# joyAnalog.net
KiCad netlist of a schematic drawn in EAGLE
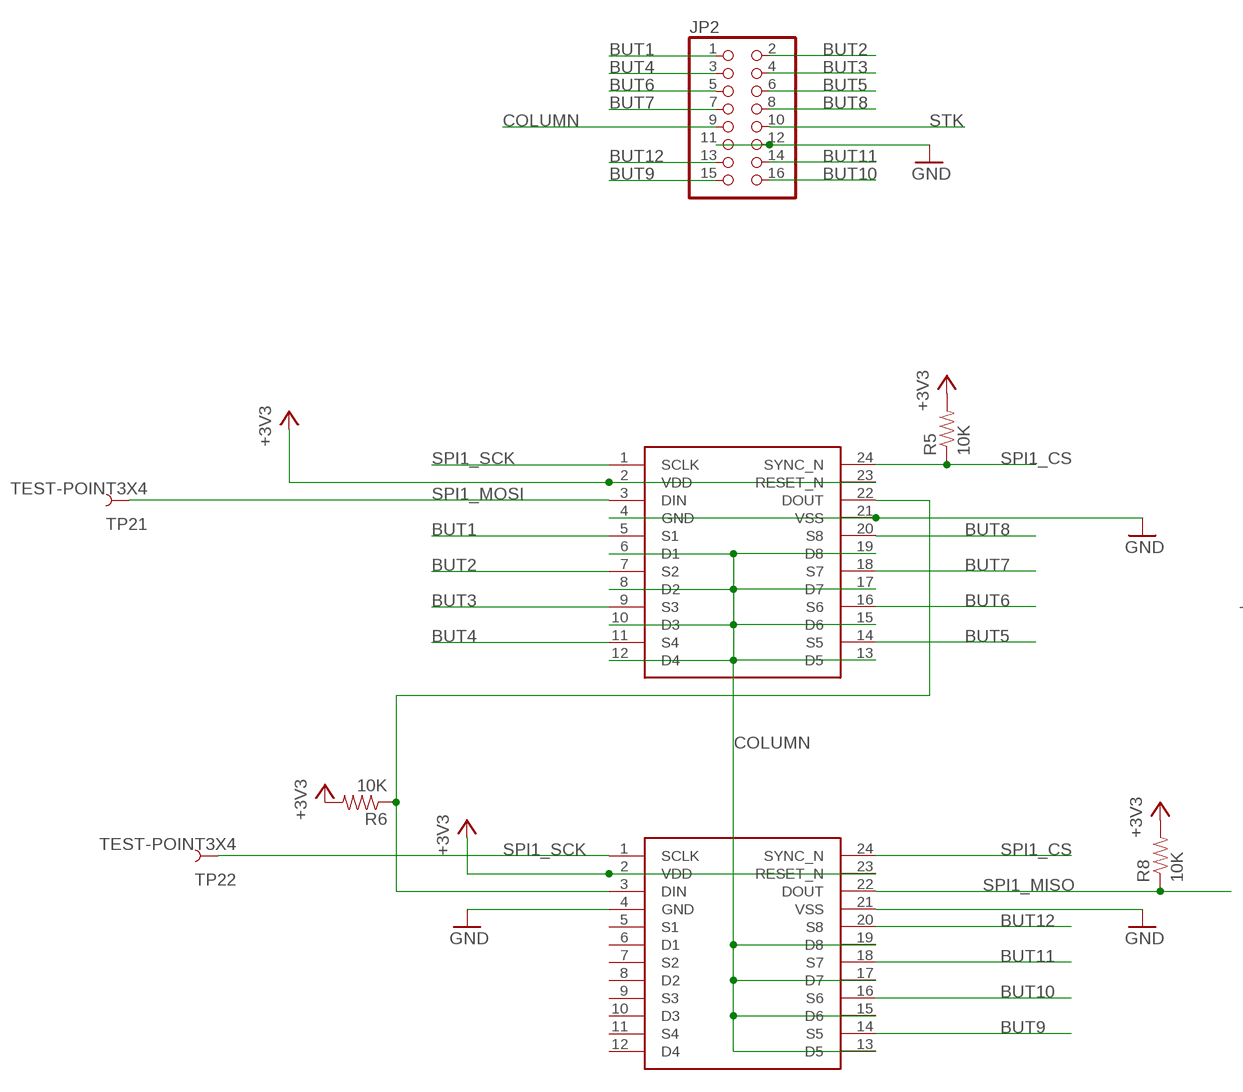
[diagram p0: schematic, sheet 1, part 1 of 2]
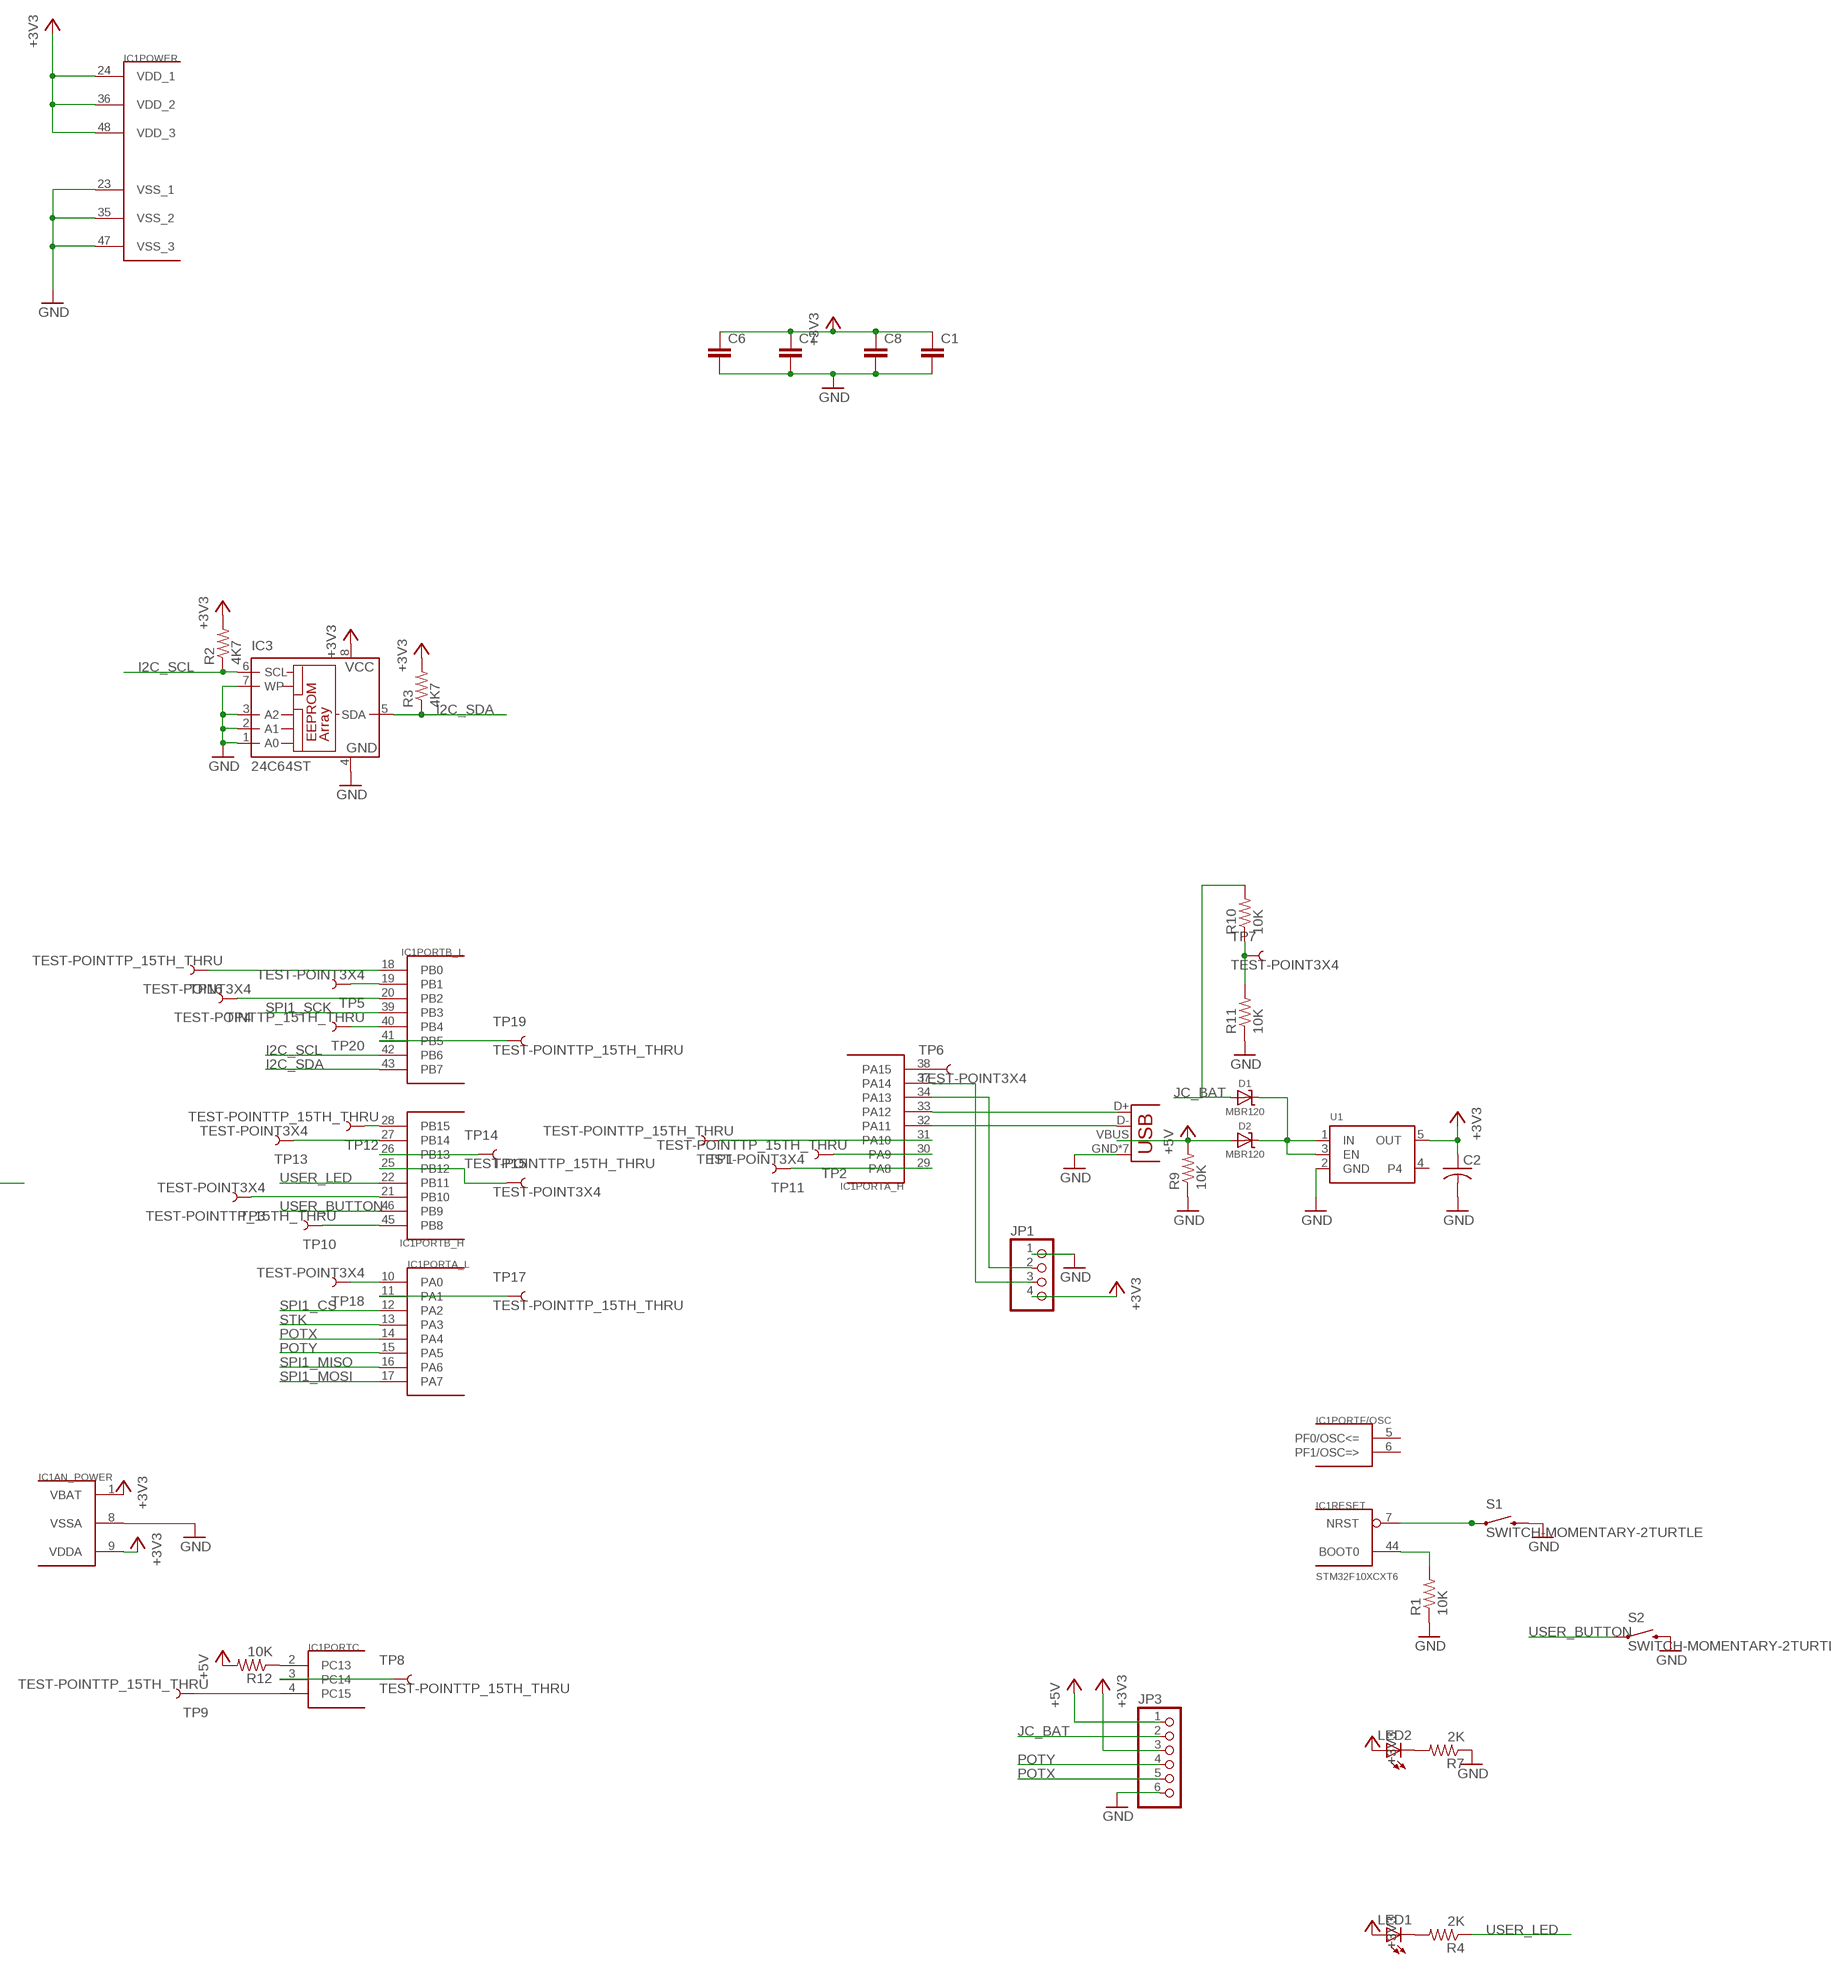
[diagram p1: schematic, sheet 1, part 2 of 2]

(export (version "E")
  (design (tool "Eeschema 10.0.6"))
  (components
    (comp (ref "C1")
      (value "CAP0805")
      (footprint "eagle-import:0805")
      (libsource (lib "eagle-import") (part "CAP0805"))
    )
    (comp (ref "C2")
      (value "C-USC1210")
      (footprint "eagle-import:C1210")
      (libsource (lib "eagle-import") (part "C-USC1210"))
    )
    (comp (ref "C6")
      (value "CAP0805")
      (footprint "eagle-import:0805")
      (libsource (lib "eagle-import") (part "CAP0805"))
    )
    (comp (ref "C7")
      (value "CAP0805")
      (footprint "eagle-import:0805")
      (libsource (lib "eagle-import") (part "CAP0805"))
    )
    (comp (ref "C8")
      (value "CAP0805")
      (footprint "eagle-import:0805")
      (libsource (lib "eagle-import") (part "CAP0805"))
    )
    (comp (ref "D1")
      (value "MBR120")
      (footprint "eagle-import:SOD-123")
      (libsource (lib "eagle-import") (part "DIODE-SCHOTTKYSOD-123"))
    )
    (comp (ref "D2")
      (value "MBR120")
      (footprint "eagle-import:SOD-123")
      (libsource (lib "eagle-import") (part "DIODE-SCHOTTKYSOD-123"))
    )
    (comp (ref "IC1")
      (value "STM32F10XCXT6")
      (footprint "eagle-import:TQFP48")
      (libsource (lib "eagle-import") (part "STM32F10XCXT6"))
    )
    (comp (ref "IC3")
      (value "24C64ST")
      (footprint "eagle-import:TSSOP8")
      (fields (field (name "MPN") "CAT24C64YI-GT3"))
      (libsource (lib "eagle-import") (part "24STC64"))
    )
    (comp (ref "JP1")
      (value "PINHD-1X4")
      (footprint "eagle-import:1X04")
      (libsource (lib "eagle-import") (part "PINHD-1X4"))
    )
    (comp (ref "JP2")
      (value "PINHD-2X8")
      (footprint "eagle-import:2X08")
      (libsource (lib "eagle-import") (part "PINHD-2X8"))
    )
    (comp (ref "JP3")
      (value "PINHD-1X6CB")
      (footprint "eagle-import:1X06-CLEANBIG")
      (libsource (lib "eagle-import") (part "PINHD-1X6CB"))
    )
    (comp (ref "LED1")
      (value "LEDCHIP-LED0805")
      (footprint "eagle-import:CHIP-LED0805")
      (libsource (lib "eagle-import") (part "LEDCHIP-LED0805"))
    )
    (comp (ref "LED2")
      (value "LEDCHIP-LED0805")
      (footprint "eagle-import:CHIP-LED0805")
      (libsource (lib "eagle-import") (part "LEDCHIP-LED0805"))
    )
    (comp (ref "R1")
      (value "10K")
      (footprint "eagle-import:0805")
      (libsource (lib "eagle-import") (part "RESISTOR0805-RES"))
    )
    (comp (ref "R2")
      (value "4K7")
      (footprint "eagle-import:0805")
      (libsource (lib "eagle-import") (part "RESISTOR0805-RES"))
    )
    (comp (ref "R3")
      (value "4K7")
      (footprint "eagle-import:0805")
      (libsource (lib "eagle-import") (part "RESISTOR0805-RES"))
    )
    (comp (ref "R4")
      (value "2K")
      (footprint "eagle-import:0805")
      (libsource (lib "eagle-import") (part "RESISTOR0805-RES"))
    )
    (comp (ref "R5")
      (value "10K")
      (footprint "eagle-import:0805")
      (libsource (lib "eagle-import") (part "RESISTOR0805-RES"))
    )
    (comp (ref "R6")
      (value "10K")
      (footprint "eagle-import:0805")
      (libsource (lib "eagle-import") (part "RESISTOR0805-RES"))
    )
    (comp (ref "R7")
      (value "2K")
      (footprint "eagle-import:0805")
      (libsource (lib "eagle-import") (part "RESISTOR0805-RES"))
    )
    (comp (ref "R8")
      (value "10K")
      (footprint "eagle-import:0805")
      (libsource (lib "eagle-import") (part "RESISTOR0805-RES"))
    )
    (comp (ref "R9")
      (value "10K")
      (footprint "eagle-import:0805")
      (libsource (lib "eagle-import") (part "RESISTOR0805-RES"))
    )
    (comp (ref "R10")
      (value "10K")
      (footprint "eagle-import:0805")
      (libsource (lib "eagle-import") (part "RESISTOR0805-RES"))
    )
    (comp (ref "R11")
      (value "10K")
      (footprint "eagle-import:0805")
      (libsource (lib "eagle-import") (part "RESISTOR0805-RES"))
    )
    (comp (ref "R12")
      (value "10K")
      (footprint "eagle-import:0805")
      (libsource (lib "eagle-import") (part "RESISTOR0805-RES"))
    )
    (comp (ref "S1")
      (value "SWITCH-MOMENTARY-2TURTLE")
      (footprint "eagle-import:KMR2")
      (libsource (lib "eagle-import") (part "SWITCH-MOMENTARY-2TURTLE"))
    )
    (comp (ref "S2")
      (value "SWITCH-MOMENTARY-2TURTLE")
      (footprint "eagle-import:KMR2")
      (libsource (lib "eagle-import") (part "SWITCH-MOMENTARY-2TURTLE"))
    )
    (comp (ref "TP1")
      (value "TEST-POINTTP_15TH_THRU")
      (footprint "eagle-import:TP_15TH")
      (libsource (lib "eagle-import") (part "pth testpoint_TEST-POINTTP_15TH_THRU"))
    )
    (comp (ref "TP2")
      (value "TEST-POINTTP_15TH_THRU")
      (footprint "eagle-import:TP_15TH")
      (libsource (lib "eagle-import") (part "pth testpoint_TEST-POINTTP_15TH_THRU"))
    )
    (comp (ref "TP3")
      (value "TEST-POINT3X4")
      (footprint "eagle-import:PAD.03X.04")
      (libsource (lib "eagle-import") (part "TEST-POINT3X4"))
    )
    (comp (ref "TP4")
      (value "TEST-POINT3X4")
      (footprint "eagle-import:PAD.03X.04")
      (libsource (lib "eagle-import") (part "TEST-POINT3X4"))
    )
    (comp (ref "TP5")
      (value "TEST-POINT3X4")
      (footprint "eagle-import:PAD.03X.04")
      (libsource (lib "eagle-import") (part "TEST-POINT3X4"))
    )
    (comp (ref "TP6")
      (value "TEST-POINT3X4")
      (footprint "eagle-import:PAD.03X.04")
      (libsource (lib "eagle-import") (part "TEST-POINT3X4"))
    )
    (comp (ref "TP7")
      (value "TEST-POINT3X4")
      (footprint "eagle-import:PAD.03X.04")
      (libsource (lib "eagle-import") (part "TEST-POINT3X4"))
    )
    (comp (ref "TP8")
      (value "TEST-POINTTP_15TH_THRU")
      (footprint "eagle-import:TP_15TH")
      (libsource (lib "eagle-import") (part "pth testpoint_TEST-POINTTP_15TH_THRU"))
    )
    (comp (ref "TP9")
      (value "TEST-POINTTP_15TH_THRU")
      (footprint "eagle-import:TP_15TH")
      (libsource (lib "eagle-import") (part "pth testpoint_TEST-POINTTP_15TH_THRU"))
    )
    (comp (ref "TP10")
      (value "TEST-POINTTP_15TH_THRU")
      (footprint "eagle-import:TP_15TH")
      (libsource (lib "eagle-import") (part "pth testpoint_TEST-POINTTP_15TH_THRU"))
    )
    (comp (ref "TP11")
      (value "TEST-POINT3X4")
      (footprint "eagle-import:PAD.03X.04")
      (libsource (lib "eagle-import") (part "TEST-POINT3X4"))
    )
    (comp (ref "TP12")
      (value "TEST-POINTTP_15TH_THRU")
      (footprint "eagle-import:TP_15TH")
      (libsource (lib "eagle-import") (part "pth testpoint_TEST-POINTTP_15TH_THRU"))
    )
    (comp (ref "TP13")
      (value "TEST-POINT3X4")
      (footprint "eagle-import:PAD.03X.04")
      (libsource (lib "eagle-import") (part "TEST-POINT3X4"))
    )
    (comp (ref "TP14")
      (value "TEST-POINTTP_15TH_THRU")
      (footprint "eagle-import:TP_15TH")
      (libsource (lib "eagle-import") (part "pth testpoint_TEST-POINTTP_15TH_THRU"))
    )
    (comp (ref "TP15")
      (value "TEST-POINT3X4")
      (footprint "eagle-import:PAD.03X.04")
      (libsource (lib "eagle-import") (part "TEST-POINT3X4"))
    )
    (comp (ref "TP16")
      (value "TEST-POINTTP_15TH_THRU")
      (footprint "eagle-import:TP_15TH")
      (libsource (lib "eagle-import") (part "pth testpoint_TEST-POINTTP_15TH_THRU"))
    )
    (comp (ref "TP17")
      (value "TEST-POINTTP_15TH_THRU")
      (footprint "eagle-import:TP_15TH")
      (libsource (lib "eagle-import") (part "pth testpoint_TEST-POINTTP_15TH_THRU"))
    )
    (comp (ref "TP18")
      (value "TEST-POINT3X4")
      (footprint "eagle-import:PAD.03X.04")
      (libsource (lib "eagle-import") (part "TEST-POINT3X4"))
    )
    (comp (ref "TP19")
      (value "TEST-POINTTP_15TH_THRU")
      (footprint "eagle-import:TP_15TH")
      (libsource (lib "eagle-import") (part "pth testpoint_TEST-POINTTP_15TH_THRU"))
    )
    (comp (ref "TP20")
      (value "TEST-POINTTP_15TH_THRU")
      (footprint "eagle-import:TP_15TH")
      (libsource (lib "eagle-import") (part "pth testpoint_TEST-POINTTP_15TH_THRU"))
    )
    (comp (ref "TP21")
      (value "TEST-POINT3X4")
      (footprint "eagle-import:PAD.03X.04")
      (libsource (lib "eagle-import") (part "TEST-POINT3X4"))
    )
    (comp (ref "TP22")
      (value "TEST-POINT3X4")
      (footprint "eagle-import:PAD.03X.04")
      (libsource (lib "eagle-import") (part "TEST-POINT3X4"))
    )
    (comp (ref "U$3")
      (value "ADG714_DEV")
      (footprint "eagle-import:TSSOP-24")
      (libsource (lib "eagle-import") (part "ADG714_DEV"))
    )
    (comp (ref "U$4")
      (value "ADG714_DEV")
      (footprint "eagle-import:TSSOP-24")
      (libsource (lib "eagle-import") (part "ADG714_DEV"))
    )
    (comp (ref "U1")
      (value "VREG_SOT23-5")
      (footprint "eagle-import:SOT23-5")
      (libsource (lib "eagle-import") (part "VREG_SOT23-5"))
    )
    (comp (ref "X1")
      (value "USB-MICROB")
      (footprint "eagle-import:USB-MICROB")
      (libsource (lib "eagle-import") (part "USB-MICROB"))
    )
  )
  (nets
    (net (code "1") (name "+3V3") (class "Default")
      (node (ref "C1") (pin "1") (pinfunction "1_1") (pintype "passive"))
      (node (ref "C2") (pin "1") (pinfunction "1_1") (pintype "passive"))
      (node (ref "C6") (pin "1") (pinfunction "1_1") (pintype "passive"))
      (node (ref "C7") (pin "1") (pinfunction "1_1") (pintype "passive"))
      (node (ref "C8") (pin "1") (pinfunction "1_1") (pintype "passive"))
      (node (ref "IC1") (pin "1") (pinfunction "VBAT_1") (pintype "power_in"))
      (node (ref "IC1") (pin "24") (pinfunction "VDD_1_24") (pintype "power_in"))
      (node (ref "IC1") (pin "36") (pinfunction "VDD_2_36") (pintype "power_in"))
      (node (ref "IC1") (pin "48") (pinfunction "VDD_3_48") (pintype "power_in"))
      (node (ref "IC1") (pin "9") (pinfunction "VDDA_9") (pintype "power_in"))
      (node (ref "IC3") (pin "8") (pinfunction "VCC_8") (pintype "power_in"))
      (node (ref "JP1") (pin "4") (pinfunction "4_4") (pintype "passive"))
      (node (ref "JP3") (pin "3") (pinfunction "3_3") (pintype "passive"))
      (node (ref "LED1") (pin "A") (pinfunction "A_A") (pintype "passive"))
      (node (ref "LED2") (pin "A") (pinfunction "A_A") (pintype "passive"))
      (node (ref "R2") (pin "2") (pinfunction "2_2") (pintype "passive"))
      (node (ref "R3") (pin "2") (pinfunction "2_2") (pintype "passive"))
      (node (ref "R5") (pin "2") (pinfunction "2_2") (pintype "passive"))
      (node (ref "R6") (pin "2") (pinfunction "2_2") (pintype "passive"))
      (node (ref "R8") (pin "2") (pinfunction "2_2") (pintype "passive"))
      (node (ref "U$3") (pin "2") (pinfunction "VDD_2") (pintype "bidirectional"))
      (node (ref "U$3") (pin "23") (pinfunction "RESET_N_23") (pintype "bidirectional"))
      (node (ref "U$4") (pin "2") (pinfunction "VDD_2") (pintype "bidirectional"))
      (node (ref "U$4") (pin "23") (pinfunction "RESET_N_23") (pintype "bidirectional"))
      (node (ref "U1") (pin "5") (pinfunction "OUT_5") (pintype "power_in"))
    )
    (net (code "2") (name "+5V") (class "Default")
      (node (ref "D2") (pin "A") (pinfunction "A_A") (pintype "passive"))
      (node (ref "JP3") (pin "1") (pinfunction "1_1") (pintype "passive"))
      (node (ref "R12") (pin "2") (pinfunction "2_2") (pintype "passive"))
      (node (ref "R9") (pin "2") (pinfunction "2_2") (pintype "passive"))
      (node (ref "X1") (pin "VBUS") (pinfunction "VBUS_VBUS") (pintype "bidirectional"))
    )
    (net (code "3") (name "/BUT1") (class "Default")
      (node (ref "JP2") (pin "1") (pinfunction "1_1") (pintype "passive"))
      (node (ref "U$3") (pin "5") (pinfunction "S1_5") (pintype "bidirectional"))
    )
    (net (code "4") (name "/BUT2") (class "Default")
      (node (ref "JP2") (pin "2") (pinfunction "2_2") (pintype "passive"))
      (node (ref "U$3") (pin "7") (pinfunction "S2_7") (pintype "bidirectional"))
    )
    (net (code "5") (name "/BUT3") (class "Default")
      (node (ref "JP2") (pin "4") (pinfunction "4_4") (pintype "passive"))
      (node (ref "U$3") (pin "9") (pinfunction "S3_9") (pintype "bidirectional"))
    )
    (net (code "6") (name "/BUT4") (class "Default")
      (node (ref "JP2") (pin "3") (pinfunction "3_3") (pintype "passive"))
      (node (ref "U$3") (pin "11") (pinfunction "S4_11") (pintype "bidirectional"))
    )
    (net (code "7") (name "/BUT5") (class "Default")
      (node (ref "JP2") (pin "6") (pinfunction "6_6") (pintype "passive"))
      (node (ref "U$3") (pin "14") (pinfunction "S5_14") (pintype "bidirectional"))
    )
    (net (code "8") (name "/BUT6") (class "Default")
      (node (ref "JP2") (pin "5") (pinfunction "5_5") (pintype "passive"))
      (node (ref "U$3") (pin "16") (pinfunction "S6_16") (pintype "bidirectional"))
    )
    (net (code "9") (name "/BUT7") (class "Default")
      (node (ref "JP2") (pin "7") (pinfunction "7_7") (pintype "passive"))
      (node (ref "U$3") (pin "18") (pinfunction "S7_18") (pintype "bidirectional"))
    )
    (net (code "10") (name "/BUT8") (class "Default")
      (node (ref "JP2") (pin "8") (pinfunction "8_8") (pintype "passive"))
      (node (ref "U$3") (pin "20") (pinfunction "S8_20") (pintype "bidirectional"))
    )
    (net (code "11") (name "/BUT9") (class "Default")
      (node (ref "JP2") (pin "15") (pinfunction "15_15") (pintype "passive"))
      (node (ref "U$4") (pin "14") (pinfunction "S5_14") (pintype "bidirectional"))
    )
    (net (code "12") (name "/BUT10") (class "Default")
      (node (ref "JP2") (pin "16") (pinfunction "16_16") (pintype "passive"))
      (node (ref "U$4") (pin "16") (pinfunction "S6_16") (pintype "bidirectional"))
    )
    (net (code "13") (name "/BUT11") (class "Default")
      (node (ref "JP2") (pin "14") (pinfunction "14_14") (pintype "passive"))
      (node (ref "U$4") (pin "18") (pinfunction "S7_18") (pintype "bidirectional"))
    )
    (net (code "14") (name "/BUT12") (class "Default")
      (node (ref "JP2") (pin "13") (pinfunction "13_13") (pintype "passive"))
      (node (ref "U$4") (pin "20") (pinfunction "S8_20") (pintype "bidirectional"))
    )
    (net (code "15") (name "/COLUMN") (class "Default")
      (node (ref "JP2") (pin "9") (pinfunction "9_9") (pintype "passive"))
      (node (ref "U$3") (pin "10") (pinfunction "D3_10") (pintype "bidirectional"))
      (node (ref "U$3") (pin "12") (pinfunction "D4_12") (pintype "bidirectional"))
      (node (ref "U$3") (pin "13") (pinfunction "D5_13") (pintype "bidirectional"))
      (node (ref "U$3") (pin "15") (pinfunction "D6_15") (pintype "bidirectional"))
      (node (ref "U$3") (pin "17") (pinfunction "D7_17") (pintype "bidirectional"))
      (node (ref "U$3") (pin "19") (pinfunction "D8_19") (pintype "bidirectional"))
      (node (ref "U$3") (pin "6") (pinfunction "D1_6") (pintype "bidirectional"))
      (node (ref "U$3") (pin "8") (pinfunction "D2_8") (pintype "bidirectional"))
      (node (ref "U$4") (pin "13") (pinfunction "D5_13") (pintype "bidirectional"))
      (node (ref "U$4") (pin "15") (pinfunction "D6_15") (pintype "bidirectional"))
      (node (ref "U$4") (pin "17") (pinfunction "D7_17") (pintype "bidirectional"))
      (node (ref "U$4") (pin "19") (pinfunction "D8_19") (pintype "bidirectional"))
    )
    (net (code "16") (name "/I2C_SCL") (class "Default")
      (node (ref "IC1") (pin "42") (pinfunction "PB6_42") (pintype "bidirectional"))
      (node (ref "IC3") (pin "6") (pinfunction "SCL_6") (pintype "input"))
      (node (ref "R2") (pin "1") (pinfunction "1_1") (pintype "passive"))
    )
    (net (code "17") (name "/I2C_SDA") (class "Default")
      (node (ref "IC1") (pin "43") (pinfunction "PB7_43") (pintype "bidirectional"))
      (node (ref "IC3") (pin "5") (pinfunction "SDA_5") (pintype "bidirectional"))
      (node (ref "R3") (pin "1") (pinfunction "1_1") (pintype "passive"))
    )
    (net (code "18") (name "/JC_BAT") (class "Default")
      (node (ref "D1") (pin "A") (pinfunction "A_A") (pintype "passive"))
      (node (ref "JP3") (pin "2") (pinfunction "2_2") (pintype "passive"))
      (node (ref "R10") (pin "2") (pinfunction "2_2") (pintype "passive"))
    )
    (net (code "19") (name "/POTX") (class "Default")
      (node (ref "IC1") (pin "14") (pinfunction "PA4_14") (pintype "bidirectional"))
      (node (ref "JP3") (pin "5") (pinfunction "5_5") (pintype "passive"))
    )
    (net (code "20") (name "/POTY") (class "Default")
      (node (ref "IC1") (pin "15") (pinfunction "PA5_15") (pintype "bidirectional"))
      (node (ref "JP3") (pin "4") (pinfunction "4_4") (pintype "passive"))
    )
    (net (code "21") (name "/SPI1_CS") (class "Default")
      (node (ref "IC1") (pin "12") (pinfunction "PA2_12") (pintype "bidirectional"))
      (node (ref "R5") (pin "1") (pinfunction "1_1") (pintype "passive"))
      (node (ref "U$3") (pin "24") (pinfunction "SYNC_N_24") (pintype "bidirectional"))
      (node (ref "U$4") (pin "24") (pinfunction "SYNC_N_24") (pintype "bidirectional"))
    )
    (net (code "22") (name "/SPI1_MISO") (class "Default")
      (node (ref "IC1") (pin "16") (pinfunction "PA6_16") (pintype "bidirectional"))
      (node (ref "R8") (pin "1") (pinfunction "1_1") (pintype "passive"))
      (node (ref "U$4") (pin "22") (pinfunction "DOUT_22") (pintype "bidirectional"))
    )
    (net (code "23") (name "/SPI1_MOSI") (class "Default")
      (node (ref "IC1") (pin "17") (pinfunction "PA7_17") (pintype "bidirectional"))
      (node (ref "TP21") (pin "P$1") (pinfunction "1_P$1") (pintype "bidirectional"))
      (node (ref "U$3") (pin "3") (pinfunction "DIN_3") (pintype "bidirectional"))
    )
    (net (code "24") (name "/SPI1_SCK") (class "Default")
      (node (ref "IC1") (pin "39") (pinfunction "PB3_39") (pintype "bidirectional"))
      (node (ref "TP22") (pin "P$1") (pinfunction "1_P$1") (pintype "bidirectional"))
      (node (ref "U$3") (pin "1") (pinfunction "SCLK_1") (pintype "bidirectional"))
      (node (ref "U$4") (pin "1") (pinfunction "SCLK_1") (pintype "bidirectional"))
    )
    (net (code "25") (name "/STK") (class "Default")
      (node (ref "IC1") (pin "13") (pinfunction "PA3_13") (pintype "bidirectional"))
      (node (ref "JP2") (pin "10") (pinfunction "10_10") (pintype "passive"))
    )
    (net (code "26") (name "/USER_BUTTON") (class "Default")
      (node (ref "IC1") (pin "46") (pinfunction "PB9_46") (pintype "bidirectional"))
      (node (ref "S2") (pin "1") (pinfunction "1_1") (pintype "passive"))
    )
    (net (code "27") (name "/USER_LED") (class "Default")
      (node (ref "IC1") (pin "22") (pinfunction "PB11_22") (pintype "bidirectional"))
      (node (ref "R4") (pin "1") (pinfunction "1_1") (pintype "passive"))
    )
    (net (code "28") (name "GND") (class "Default")
      (node (ref "C1") (pin "2") (pinfunction "2_2") (pintype "passive"))
      (node (ref "C2") (pin "2") (pinfunction "2_2") (pintype "passive"))
      (node (ref "C6") (pin "2") (pinfunction "2_2") (pintype "passive"))
      (node (ref "C7") (pin "2") (pinfunction "2_2") (pintype "passive"))
      (node (ref "C8") (pin "2") (pinfunction "2_2") (pintype "passive"))
      (node (ref "IC1") (pin "23") (pinfunction "VSS_1_23") (pintype "power_in"))
      (node (ref "IC1") (pin "35") (pinfunction "VSS_2_35") (pintype "power_in"))
      (node (ref "IC1") (pin "47") (pinfunction "VSS_3_47") (pintype "power_in"))
      (node (ref "IC1") (pin "8") (pinfunction "VSSA_8") (pintype "power_in"))
      (node (ref "IC3") (pin "1") (pinfunction "A0_1") (pintype "input"))
      (node (ref "IC3") (pin "2") (pinfunction "A1_2") (pintype "input"))
      (node (ref "IC3") (pin "3") (pinfunction "A2_3") (pintype "input"))
      (node (ref "IC3") (pin "4") (pinfunction "GND_4") (pintype "power_in"))
      (node (ref "IC3") (pin "7") (pinfunction "WP_7") (pintype "input"))
      (node (ref "JP1") (pin "1") (pinfunction "1_1") (pintype "passive"))
      (node (ref "JP2") (pin "11") (pinfunction "11_11") (pintype "passive"))
      (node (ref "JP2") (pin "12") (pinfunction "12_12") (pintype "passive"))
      (node (ref "JP3") (pin "6") (pinfunction "6_6") (pintype "passive"))
      (node (ref "R1") (pin "1") (pinfunction "1_1") (pintype "passive"))
      (node (ref "R11") (pin "1") (pinfunction "1_1") (pintype "passive"))
      (node (ref "R7") (pin "1") (pinfunction "1_1") (pintype "passive"))
      (node (ref "R9") (pin "1") (pinfunction "1_1") (pintype "passive"))
      (node (ref "S1") (pin "3") (pinfunction "2_3") (pintype "passive"))
      (node (ref "S2") (pin "3") (pinfunction "2_3") (pintype "passive"))
      (node (ref "U$3") (pin "21") (pinfunction "VSS_21") (pintype "bidirectional"))
      (node (ref "U$3") (pin "4") (pinfunction "GND_4") (pintype "bidirectional"))
      (node (ref "U$4") (pin "21") (pinfunction "VSS_21") (pintype "bidirectional"))
      (node (ref "U$4") (pin "4") (pinfunction "GND_4") (pintype "bidirectional"))
      (node (ref "U1") (pin "2") (pinfunction "GND_2") (pintype "power_in"))
      (node (ref "X1") (pin "GND") (pinfunction "GND_GND") (pintype "bidirectional"))
      (node (ref "X1") (pin "P1") (pinfunction "GND_P1") (pintype "bidirectional"))
      (node (ref "X1") (pin "P2") (pinfunction "GND_P2") (pintype "bidirectional"))
      (node (ref "X1") (pin "P3") (pinfunction "GND_P3") (pintype "bidirectional"))
      (node (ref "X1") (pin "P4") (pinfunction "GND_P4") (pintype "bidirectional"))
      (node (ref "X1") (pin "P5") (pinfunction "GND_P5") (pintype "bidirectional"))
      (node (ref "X1") (pin "P6") (pinfunction "GND_P6") (pintype "bidirectional"))
    )
    (net (code "29") (name "Net-(IC1B-PA8)") (class "Default")
      (node (ref "IC1") (pin "29") (pinfunction "PA8_29") (pintype "bidirectional"))
      (node (ref "TP11") (pin "P$1") (pinfunction "1_P$1") (pintype "bidirectional"))
    )
    (net (code "30") (name "Net-(IC1B-PA9)") (class "Default")
      (node (ref "IC1") (pin "30") (pinfunction "PA9_30") (pintype "bidirectional"))
      (node (ref "TP2") (pin "P$1") (pinfunction "1_P$1") (pintype "bidirectional"))
    )
    (net (code "31") (name "Net-(IC1B-PA10)") (class "Default")
      (node (ref "IC1") (pin "31") (pinfunction "PA10_31") (pintype "bidirectional"))
      (node (ref "TP1") (pin "P$1") (pinfunction "1_P$1") (pintype "bidirectional"))
    )
    (net (code "32") (name "Net-(IC1B-PA11)") (class "Default")
      (node (ref "IC1") (pin "32") (pinfunction "PA11_32") (pintype "bidirectional"))
      (node (ref "X1") (pin "D-") (pinfunction "D-_D-") (pintype "bidirectional"))
    )
    (net (code "33") (name "Net-(IC1B-PA12)") (class "Default")
      (node (ref "IC1") (pin "33") (pinfunction "PA12_33") (pintype "bidirectional"))
      (node (ref "X1") (pin "D+") (pinfunction "D+_D+") (pintype "bidirectional"))
    )
    (net (code "34") (name "Net-(IC1B-PA13)") (class "Default")
      (node (ref "IC1") (pin "34") (pinfunction "PA13_34") (pintype "bidirectional"))
      (node (ref "JP1") (pin "2") (pinfunction "2_2") (pintype "passive"))
    )
    (net (code "35") (name "Net-(IC1B-PA14)") (class "Default")
      (node (ref "IC1") (pin "37") (pinfunction "PA14_37") (pintype "bidirectional"))
      (node (ref "JP1") (pin "3") (pinfunction "3_3") (pintype "passive"))
    )
    (net (code "36") (name "Net-(IC1B-PA15)") (class "Default")
      (node (ref "IC1") (pin "38") (pinfunction "PA15_38") (pintype "bidirectional"))
      (node (ref "TP6") (pin "P$1") (pinfunction "1_P$1") (pintype "bidirectional"))
    )
    (net (code "37") (name "Net-(IC1C-PA0)") (class "Default")
      (node (ref "IC1") (pin "10") (pinfunction "PA0_10") (pintype "bidirectional"))
      (node (ref "TP18") (pin "P$1") (pinfunction "1_P$1") (pintype "bidirectional"))
    )
    (net (code "38") (name "Net-(IC1C-PA1)") (class "Default")
      (node (ref "IC1") (pin "11") (pinfunction "PA1_11") (pintype "bidirectional"))
      (node (ref "TP17") (pin "P$1") (pinfunction "1_P$1") (pintype "bidirectional"))
    )
    (net (code "39") (name "Net-(IC1D-PB8)") (class "Default")
      (node (ref "IC1") (pin "45") (pinfunction "PB8_45") (pintype "bidirectional"))
      (node (ref "TP10") (pin "P$1") (pinfunction "1_P$1") (pintype "bidirectional"))
    )
    (net (code "40") (name "Net-(IC1D-PB10)") (class "Default")
      (node (ref "IC1") (pin "21") (pinfunction "PB10_21") (pintype "bidirectional"))
      (node (ref "TP3") (pin "P$1") (pinfunction "1_P$1") (pintype "bidirectional"))
    )
    (net (code "41") (name "Net-(IC1D-PB12)") (class "Default")
      (node (ref "IC1") (pin "25") (pinfunction "PB12_25") (pintype "bidirectional"))
      (node (ref "TP15") (pin "P$1") (pinfunction "1_P$1") (pintype "bidirectional"))
    )
    (net (code "42") (name "Net-(IC1D-PB13)") (class "Default")
      (node (ref "IC1") (pin "26") (pinfunction "PB13_26") (pintype "bidirectional"))
      (node (ref "TP14") (pin "P$1") (pinfunction "1_P$1") (pintype "bidirectional"))
    )
    (net (code "43") (name "Net-(IC1D-PB14)") (class "Default")
      (node (ref "IC1") (pin "27") (pinfunction "PB14_27") (pintype "bidirectional"))
      (node (ref "TP13") (pin "P$1") (pinfunction "1_P$1") (pintype "bidirectional"))
    )
    (net (code "44") (name "Net-(IC1D-PB15)") (class "Default")
      (node (ref "IC1") (pin "28") (pinfunction "PB15_28") (pintype "bidirectional"))
      (node (ref "TP12") (pin "P$1") (pinfunction "1_P$1") (pintype "bidirectional"))
    )
    (net (code "45") (name "Net-(IC1E-PB0)") (class "Default")
      (node (ref "IC1") (pin "18") (pinfunction "PB0_18") (pintype "bidirectional"))
      (node (ref "TP16") (pin "P$1") (pinfunction "1_P$1") (pintype "bidirectional"))
    )
    (net (code "46") (name "Net-(IC1E-PB1)") (class "Default")
      (node (ref "IC1") (pin "19") (pinfunction "PB1_19") (pintype "bidirectional"))
      (node (ref "TP5") (pin "P$1") (pinfunction "1_P$1") (pintype "bidirectional"))
    )
    (net (code "47") (name "Net-(IC1E-PB2)") (class "Default")
      (node (ref "IC1") (pin "20") (pinfunction "PB2_20") (pintype "bidirectional"))
      (node (ref "TP4") (pin "P$1") (pinfunction "1_P$1") (pintype "bidirectional"))
    )
    (net (code "48") (name "Net-(IC1E-PB4)") (class "Default")
      (node (ref "IC1") (pin "40") (pinfunction "PB4_40") (pintype "bidirectional"))
      (node (ref "TP20") (pin "P$1") (pinfunction "1_P$1") (pintype "bidirectional"))
    )
    (net (code "49") (name "Net-(IC1E-PB5)") (class "Default")
      (node (ref "IC1") (pin "41") (pinfunction "PB5_41") (pintype "bidirectional"))
      (node (ref "TP19") (pin "P$1") (pinfunction "1_P$1") (pintype "bidirectional"))
    )
    (net (code "50") (name "Net-(IC1F-PC13)") (class "Default")
      (node (ref "IC1") (pin "2") (pinfunction "PC13_2") (pintype "bidirectional"))
      (node (ref "R12") (pin "1") (pinfunction "1_1") (pintype "passive"))
    )
    (net (code "51") (name "Net-(IC1F-PC14)") (class "Default")
      (node (ref "IC1") (pin "3") (pinfunction "PC14_3") (pintype "bidirectional"))
      (node (ref "TP8") (pin "P$1") (pinfunction "1_P$1") (pintype "bidirectional"))
    )
    (net (code "52") (name "Net-(IC1F-PC15)") (class "Default")
      (node (ref "IC1") (pin "4") (pinfunction "PC15_4") (pintype "bidirectional"))
      (node (ref "TP9") (pin "P$1") (pinfunction "1_P$1") (pintype "bidirectional"))
    )
    (net (code "53") (name "Net-(IC1I-BOOT0)") (class "Default")
      (node (ref "IC1") (pin "44") (pinfunction "BOOT0_44") (pintype "input"))
      (node (ref "R1") (pin "2") (pinfunction "2_2") (pintype "passive"))
    )
    (net (code "54") (name "Net-(IC1I-NRST)") (class "Default")
      (node (ref "IC1") (pin "7") (pinfunction "NRST_7") (pintype "input"))
      (node (ref "S1") (pin "1") (pinfunction "1_1") (pintype "passive"))
    )
    (net (code "55") (name "Net-(LED1-PadC)") (class "Default")
      (node (ref "LED1") (pin "C") (pinfunction "C_C") (pintype "passive"))
      (node (ref "R4") (pin "2") (pinfunction "2_2") (pintype "passive"))
    )
    (net (code "56") (name "Net-(LED2-PadC)") (class "Default")
      (node (ref "LED2") (pin "C") (pinfunction "C_C") (pintype "passive"))
      (node (ref "R7") (pin "2") (pinfunction "2_2") (pintype "passive"))
    )
    (net (code "57") (name "Net-(TP7-1)") (class "Default")
      (node (ref "R10") (pin "1") (pinfunction "1_1") (pintype "passive"))
      (node (ref "R11") (pin "2") (pinfunction "2_2") (pintype "passive"))
      (node (ref "TP7") (pin "P$1") (pinfunction "1_P$1") (pintype "bidirectional"))
    )
    (net (code "58") (name "Net-(U$3-DOUT)") (class "Default")
      (node (ref "R6") (pin "1") (pinfunction "1_1") (pintype "passive"))
      (node (ref "U$3") (pin "22") (pinfunction "DOUT_22") (pintype "bidirectional"))
      (node (ref "U$4") (pin "3") (pinfunction "DIN_3") (pintype "bidirectional"))
    )
    (net (code "59") (name "Net-(U1-EN)") (class "Default")
      (node (ref "D1") (pin "C") (pinfunction "C_C") (pintype "passive"))
      (node (ref "D2") (pin "C") (pinfunction "C_C") (pintype "passive"))
      (node (ref "U1") (pin "1") (pinfunction "IN_1") (pintype "power_in"))
      (node (ref "U1") (pin "3") (pinfunction "EN_3") (pintype "input"))
    )
    (net (code "60") (name "unconnected-(IC1G-PF0{slash}OSC<=-Pad5)") (class "Default")
      (node (ref "IC1") (pin "5") (pinfunction "PF0/OSC<=_5") (pintype "bidirectional"))
    )
    (net (code "61") (name "unconnected-(IC1G-PF1{slash}OSC=>-Pad6)") (class "Default")
      (node (ref "IC1") (pin "6") (pinfunction "PF1/OSC=>_6") (pintype "bidirectional"))
    )
    (net (code "62") (name "unconnected-(U$4-D1-Pad6)") (class "Default")
      (node (ref "U$4") (pin "6") (pinfunction "D1_6") (pintype "bidirectional"))
    )
    (net (code "63") (name "unconnected-(U$4-D2-Pad8)") (class "Default")
      (node (ref "U$4") (pin "8") (pinfunction "D2_8") (pintype "bidirectional"))
    )
    (net (code "64") (name "unconnected-(U$4-D3-Pad10)") (class "Default")
      (node (ref "U$4") (pin "10") (pinfunction "D3_10") (pintype "bidirectional"))
    )
    (net (code "65") (name "unconnected-(U$4-D4-Pad12)") (class "Default")
      (node (ref "U$4") (pin "12") (pinfunction "D4_12") (pintype "bidirectional"))
    )
    (net (code "66") (name "unconnected-(U$4-S1-Pad5)") (class "Default")
      (node (ref "U$4") (pin "5") (pinfunction "S1_5") (pintype "bidirectional"))
    )
    (net (code "67") (name "unconnected-(U$4-S2-Pad7)") (class "Default")
      (node (ref "U$4") (pin "7") (pinfunction "S2_7") (pintype "bidirectional"))
    )
    (net (code "68") (name "unconnected-(U$4-S3-Pad9)") (class "Default")
      (node (ref "U$4") (pin "9") (pinfunction "S3_9") (pintype "bidirectional"))
    )
    (net (code "69") (name "unconnected-(U$4-S4-Pad11)") (class "Default")
      (node (ref "U$4") (pin "11") (pinfunction "S4_11") (pintype "bidirectional"))
    )
    (net (code "70") (name "unconnected-(U1-P4-Pad4)") (class "Default")
      (node (ref "U1") (pin "4") (pinfunction "P4_4") (pintype "bidirectional"))
    )
  )
)
